# ANDS_2610_Lensmount.net
KiCad netlist of a schematic drawn in EAGLE
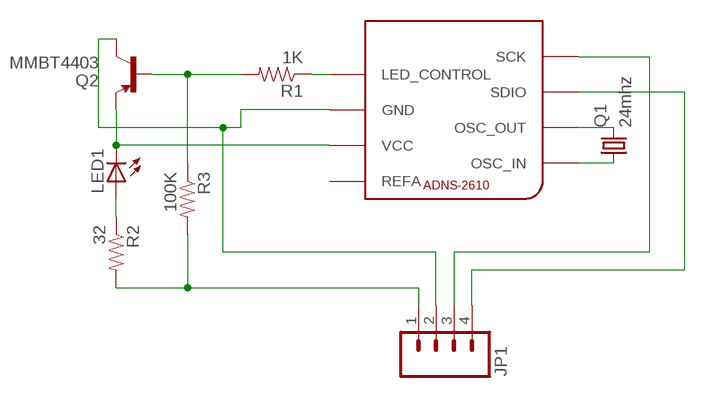
[diagram p0: schematic, sheet 1]

(export (version "E")
  (design (tool "Eeschema 10.0.6"))
  (components
    (comp (ref "JP1")
      (value "M04PTH")
      (footprint "eagle-import:1X04")
      (libsource (lib "eagle-import") (part "M04PTH"))
    )
    (comp (ref "LED1")
      (value "LED3MM")
      (footprint "eagle-import:LED3MM")
      (libsource (lib "eagle-import") (part "LED3MM"))
    )
    (comp (ref "Q1")
      (value "24mhz")
      (footprint "eagle-import:HC49_S")
      (libsource (lib "eagle-import") (part "CRYSTALHC49S"))
    )
    (comp (ref "Q2")
      (value "MMBT4403")
      (footprint "eagle-import:SOT23-3")
      (libsource (lib "eagle-import") (part "TRANSISTOR_PNPMMBT4403"))
    )
    (comp (ref "R1")
      (value "1K")
      (footprint "eagle-import:1206")
      (libsource (lib "eagle-import") (part "RESISTOR1206"))
    )
    (comp (ref "R2")
      (value "32")
      (footprint "eagle-import:1206")
      (libsource (lib "eagle-import") (part "RESISTOR1206"))
    )
    (comp (ref "R3")
      (value "100K")
      (footprint "eagle-import:1206")
      (libsource (lib "eagle-import") (part "RESISTOR1206"))
    )
    (comp (ref "U$1")
      (value "ADNS-2610")
      (footprint "eagle-import:ADNS-2610")
      (libsource (lib "eagle-import") (part "ADNS-2610"))
    )
  )
  (nets
    (net (code "1") (name "Net-(JP1-Pad1)") (class "Default")
      (node (ref "JP1") (pin "1") (pinfunction "1_1") (pintype "passive"))
      (node (ref "R2") (pin "2") (pinfunction "2_2") (pintype "passive"))
      (node (ref "R3") (pin "2") (pinfunction "2_2") (pintype "passive"))
    )
    (net (code "2") (name "Net-(JP1-Pad3)") (class "Default")
      (node (ref "JP1") (pin "3") (pinfunction "3_3") (pintype "passive"))
      (node (ref "U$1") (pin "SCK") (pinfunction "SCK_SCK") (pintype "bidirectional"))
    )
    (net (code "3") (name "Net-(JP1-Pad4)") (class "Default")
      (node (ref "JP1") (pin "4") (pinfunction "4_4") (pintype "passive"))
      (node (ref "U$1") (pin "SDIO") (pinfunction "SDIO_SDIO") (pintype "bidirectional"))
    )
    (net (code "4") (name "Net-(LED1-C)") (class "Default")
      (node (ref "LED1") (pin "K") (pinfunction "C_K") (pintype "passive"))
      (node (ref "Q2") (pin "2") (pinfunction "E_2") (pintype "passive"))
      (node (ref "U$1") (pin "VCC") (pinfunction "VCC_VCC") (pintype "bidirectional"))
    )
    (net (code "5") (name "Net-(LED1-PadA)") (class "Default")
      (node (ref "LED1") (pin "A") (pinfunction "A_A") (pintype "passive"))
      (node (ref "R2") (pin "1") (pinfunction "1_1") (pintype "passive"))
    )
    (net (code "6") (name "Net-(Q1-Pad1)") (class "Default")
      (node (ref "Q1") (pin "1") (pinfunction "1_1") (pintype "passive"))
      (node (ref "U$1") (pin "OSC_IN") (pinfunction "OSC_IN_OSC_IN") (pintype "bidirectional"))
    )
    (net (code "7") (name "Net-(Q1-Pad2)") (class "Default")
      (node (ref "Q1") (pin "2") (pinfunction "2_2") (pintype "passive"))
      (node (ref "U$1") (pin "OSC_OUT") (pinfunction "OSC_OUT_OSC_OUT") (pintype "bidirectional"))
    )
    (net (code "8") (name "Net-(Q2-B)") (class "Default")
      (node (ref "Q2") (pin "1") (pinfunction "B_1") (pintype "passive"))
      (node (ref "R1") (pin "2") (pinfunction "2_2") (pintype "passive"))
      (node (ref "R3") (pin "1") (pinfunction "1_1") (pintype "passive"))
    )
    (net (code "9") (name "Net-(Q2-C)") (class "Default")
      (node (ref "JP1") (pin "2") (pinfunction "2_2") (pintype "passive"))
      (node (ref "Q2") (pin "3") (pinfunction "C_3") (pintype "passive"))
      (node (ref "U$1") (pin "GND") (pinfunction "GND_GND") (pintype "bidirectional"))
    )
    (net (code "10") (name "Net-(R1-Pad1)") (class "Default")
      (node (ref "R1") (pin "1") (pinfunction "1_1") (pintype "passive"))
      (node (ref "U$1") (pin "LED_CONTROL") (pinfunction "LED_CONTROL_LED_CONTROL") (pintype "bidirectional"))
    )
    (net (code "11") (name "unconnected-(U$1-PadREFA)") (class "Default")
      (node (ref "U$1") (pin "REFA") (pinfunction "REFA_REFA") (pintype "bidirectional"))
    )
  )
)
